# OMODRI_EnDATEnc.net
KiCad netlist of a schematic drawn in Altium Designer
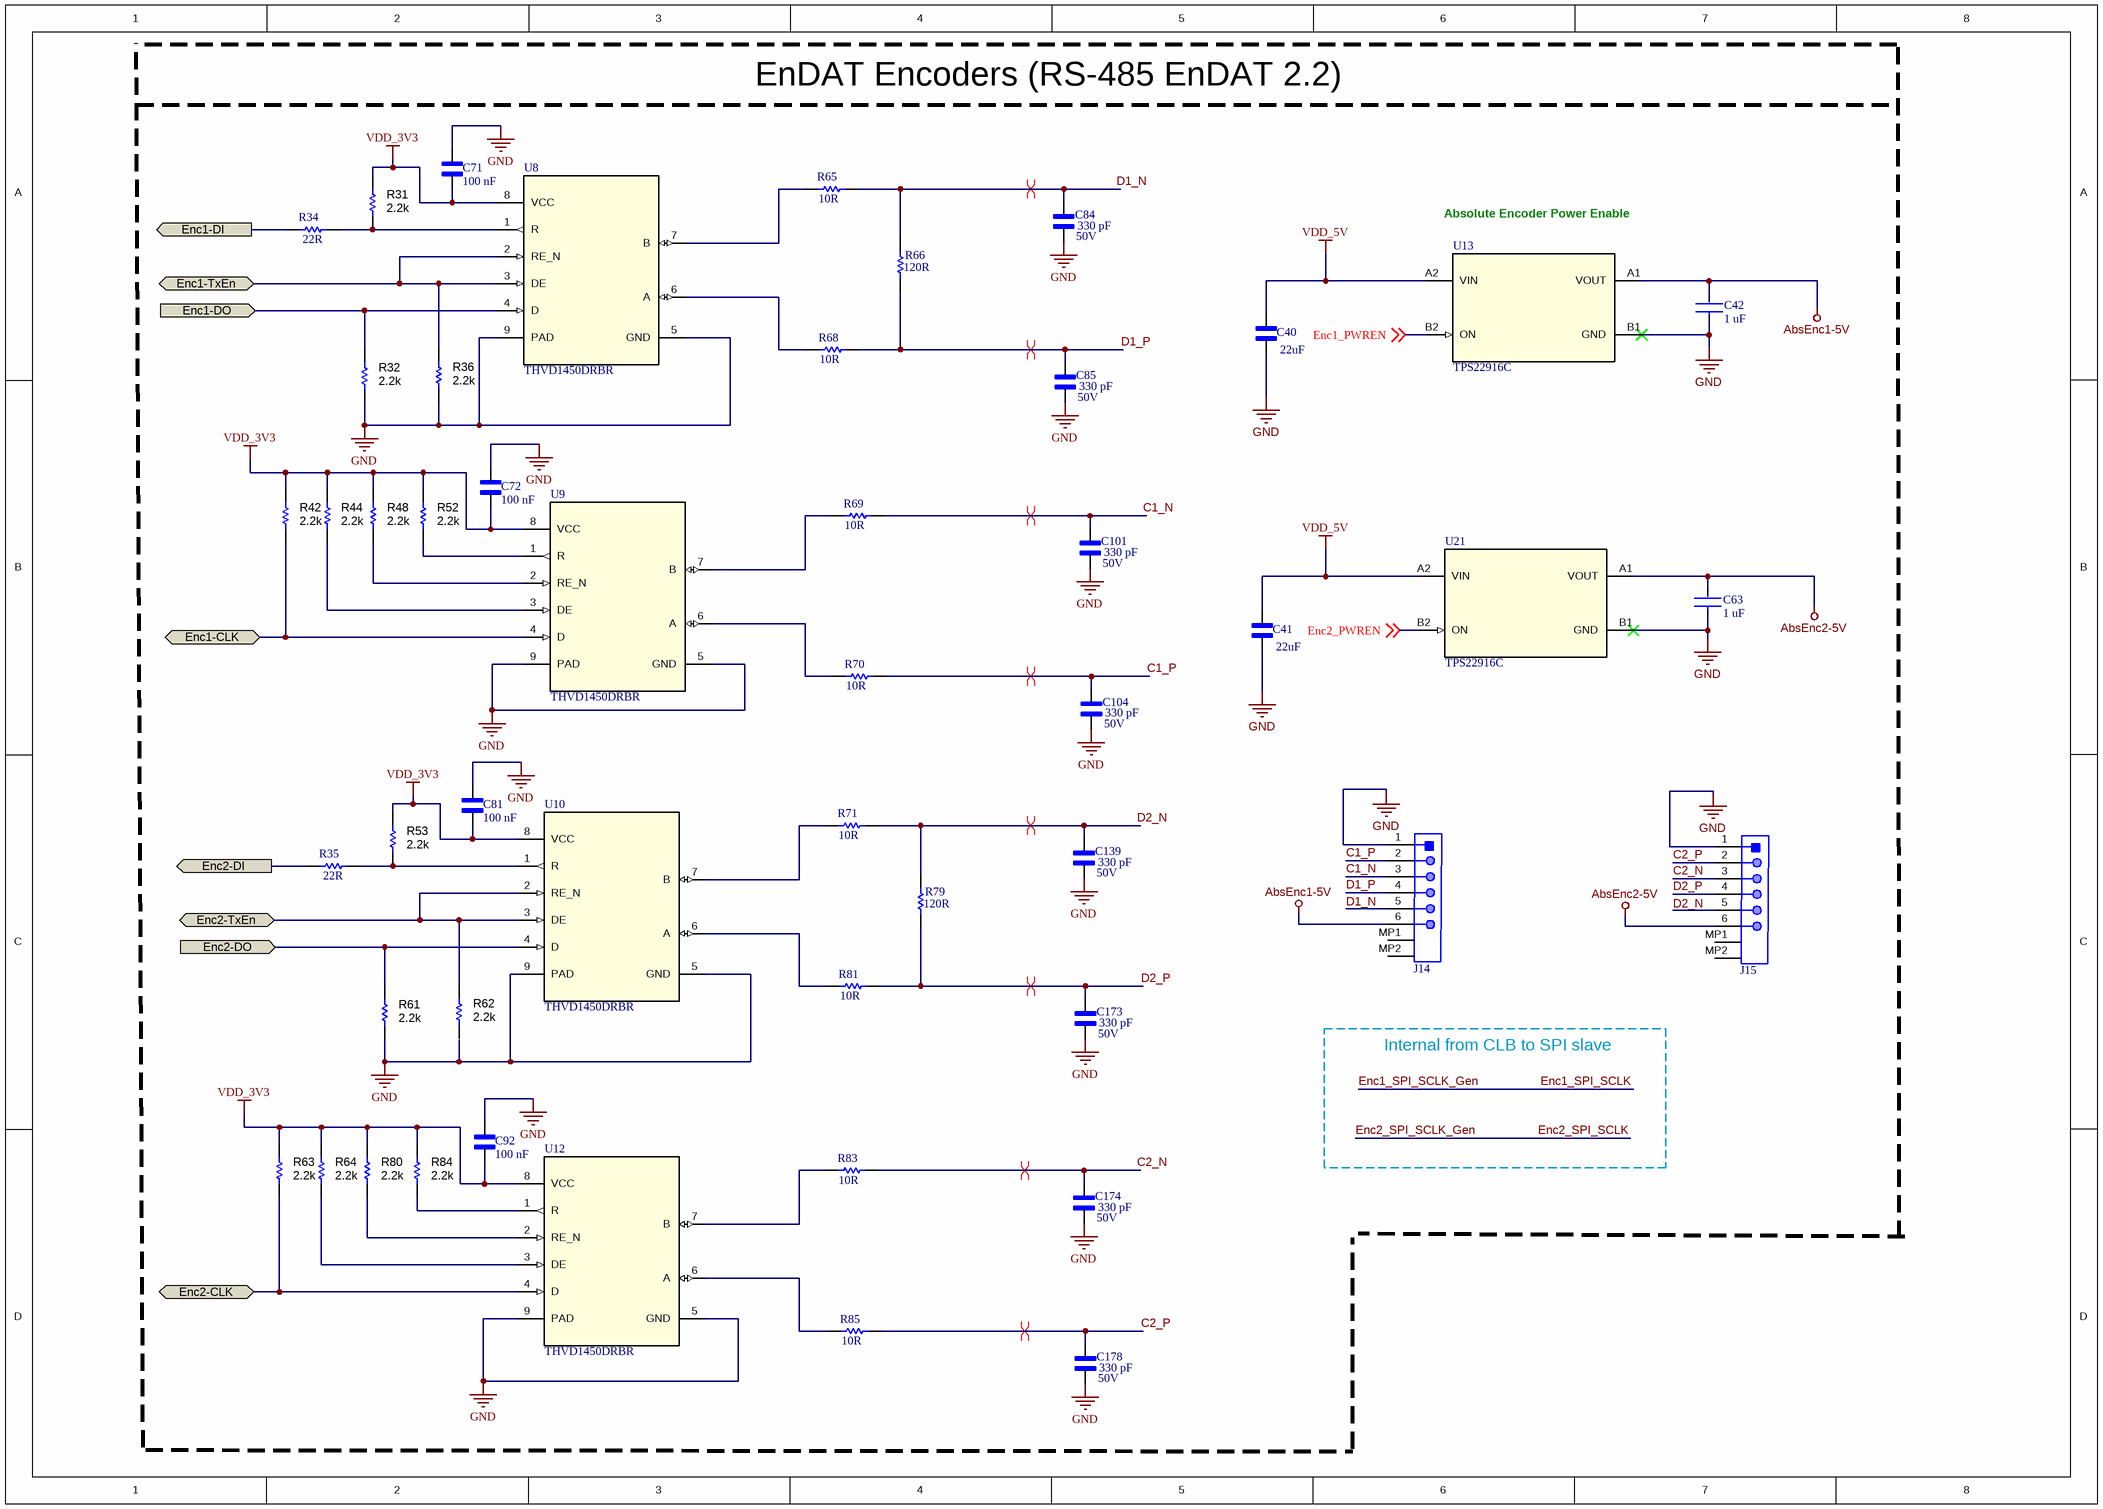
[diagram p0: OMODRI_EnDATEnc.SchDoc]

(export (version "E")
  (design (tool "Eeschema 10.0.6"))
  (components
    (comp (ref "C40")
      (value "22uF")
      (footprint "CAPC1005X55N")
      (description "22µF ±20% 6.3V Ceramic Capacitor X5R 0402 (1005 Metric)")
      (fields (field (name "MP") "CL05A226MQ5N6J8") (field (name "MF") "Samsung Electro-Mechanics"))
      (libsource (lib "CL05A226MQ5N6J8") (part "CL05A226MQ5N6J8"))
    )
    (comp (ref "C41")
      (value "22uF")
      (footprint "CAPC1005X55N")
      (description "22µF ±20% 6.3V Ceramic Capacitor X5R 0402 (1005 Metric)")
      (fields (field (name "MP") "CL05A226MQ5N6J8") (field (name "MF") "Samsung Electro-Mechanics"))
      (libsource (lib "CL05A226MQ5N6J8") (part "CL05A226MQ5N6J8"))
    )
    (comp (ref "C42")
      (value "1 uF")
      (footprint "FP-CC0201-BA-MFG")
      (description "CAP CER 1UF 6.3V X5R 0201")
      (fields (field (name "TOLERANCE") "0.2") (field (name "MANUFACTURER") "Yageo"))
      (libsource (lib "Altium Content Vault") (part "11868f565c42a9108669ba33697ecf6"))
    )
    (comp (ref "C63")
      (value "1 uF")
      (footprint "FP-CC0201-BA-MFG")
      (description "CAP CER 1UF 6.3V X5R 0201")
      (fields (field (name "TOLERANCE") "0.2") (field (name "MANUFACTURER") "Yageo"))
      (libsource (lib "Altium Content Vault") (part "11868f565c42a9108669ba33697ecf6"))
    )
    (comp (ref "C71")
      (value "100 nF")
      (footprint "CAPC0603X33N")
      (description "SMD Capacitor X5R_EIA_ with Capacitance: 0.10uF Tol. 10%. Rated Voltage: 25Vdc")
      (fields (field (name "MF") "Murata") (field (name "MP") "GRM033R61E104KE14D"))
      (libsource (lib "GRM033R61E104KE14D") (part "GRM033R61E104KE14D"))
    )
    (comp (ref "C72")
      (value "100 nF")
      (footprint "CAPC0603X33N")
      (description "SMD Capacitor X5R_EIA_ with Capacitance: 0.10uF Tol. 10%. Rated Voltage: 25Vdc")
      (fields (field (name "MF") "Murata") (field (name "MP") "GRM033R61E104KE14D"))
      (libsource (lib "GRM033R61E104KE14D") (part "GRM033R61E104KE14D"))
    )
    (comp (ref "C81")
      (value "100 nF")
      (footprint "CAPC0603X33N")
      (description "SMD Capacitor X5R_EIA_ with Capacitance: 0.10uF Tol. 10%. Rated Voltage: 25Vdc")
      (fields (field (name "MF") "Murata") (field (name "MP") "GRM033R61E104KE14D"))
      (libsource (lib "GRM033R61E104KE14D") (part "GRM033R61E104KE14D"))
    )
    (comp (ref "C84")
      (value "330 pF")
      (footprint "CAPC0603X33N")
      (description "SMD Capacitor X7R_EIA_ with Capacitance: 330pF Tol. 10%. Rated Voltage: 50Vdc")
      (fields
        (field (name "MP") "GRM033R71H331KA12D")
        (field (name "DIGI-KEY_PART_NUMBER") "490-17085-1-ND")
        (field (name "VOLTAGE") "50V")
      )
      (libsource (lib "GRM033R71H331KA12D") (part "GRM033R71H331KA12D"))
    )
    (comp (ref "C85")
      (value "330 pF")
      (footprint "CAPC0603X33N")
      (description "SMD Capacitor X7R_EIA_ with Capacitance: 330pF Tol. 10%. Rated Voltage: 50Vdc")
      (fields
        (field (name "MP") "GRM033R71H331KA12D")
        (field (name "DIGI-KEY_PART_NUMBER") "490-17085-1-ND")
        (field (name "VOLTAGE") "50V")
      )
      (libsource (lib "GRM033R71H331KA12D") (part "GRM033R71H331KA12D"))
    )
    (comp (ref "C92")
      (value "100 nF")
      (footprint "CAPC0603X33N")
      (description "SMD Capacitor X5R_EIA_ with Capacitance: 0.10uF Tol. 10%. Rated Voltage: 25Vdc")
      (fields (field (name "MF") "Murata") (field (name "MP") "GRM033R61E104KE14D"))
      (libsource (lib "GRM033R61E104KE14D") (part "GRM033R61E104KE14D"))
    )
    (comp (ref "C101")
      (value "330 pF")
      (footprint "CAPC0603X33N")
      (description "SMD Capacitor X7R_EIA_ with Capacitance: 330pF Tol. 10%. Rated Voltage: 50Vdc")
      (fields
        (field (name "MP") "GRM033R71H331KA12D")
        (field (name "DIGI-KEY_PART_NUMBER") "490-17085-1-ND")
        (field (name "VOLTAGE") "50V")
      )
      (libsource (lib "GRM033R71H331KA12D") (part "GRM033R71H331KA12D"))
    )
    (comp (ref "C104")
      (value "330 pF")
      (footprint "CAPC0603X33N")
      (description "SMD Capacitor X7R_EIA_ with Capacitance: 330pF Tol. 10%. Rated Voltage: 50Vdc")
      (fields
        (field (name "MP") "GRM033R71H331KA12D")
        (field (name "DIGI-KEY_PART_NUMBER") "490-17085-1-ND")
        (field (name "VOLTAGE") "50V")
      )
      (libsource (lib "GRM033R71H331KA12D") (part "GRM033R71H331KA12D"))
    )
    (comp (ref "C139")
      (value "330 pF")
      (footprint "CAPC0603X33N")
      (description "SMD Capacitor X7R_EIA_ with Capacitance: 330pF Tol. 10%. Rated Voltage: 50Vdc")
      (fields
        (field (name "MP") "GRM033R71H331KA12D")
        (field (name "DIGI-KEY_PART_NUMBER") "490-17085-1-ND")
        (field (name "VOLTAGE") "50V")
      )
      (libsource (lib "GRM033R71H331KA12D") (part "GRM033R71H331KA12D"))
    )
    (comp (ref "C173")
      (value "330 pF")
      (footprint "CAPC0603X33N")
      (description "SMD Capacitor X7R_EIA_ with Capacitance: 330pF Tol. 10%. Rated Voltage: 50Vdc")
      (fields
        (field (name "MP") "GRM033R71H331KA12D")
        (field (name "DIGI-KEY_PART_NUMBER") "490-17085-1-ND")
        (field (name "VOLTAGE") "50V")
      )
      (libsource (lib "GRM033R71H331KA12D") (part "GRM033R71H331KA12D"))
    )
    (comp (ref "C174")
      (value "330 pF")
      (footprint "CAPC0603X33N")
      (description "SMD Capacitor X7R_EIA_ with Capacitance: 330pF Tol. 10%. Rated Voltage: 50Vdc")
      (fields
        (field (name "MP") "GRM033R71H331KA12D")
        (field (name "DIGI-KEY_PART_NUMBER") "490-17085-1-ND")
        (field (name "VOLTAGE") "50V")
      )
      (libsource (lib "GRM033R71H331KA12D") (part "GRM033R71H331KA12D"))
    )
    (comp (ref "C178")
      (value "330 pF")
      (footprint "CAPC0603X33N")
      (description "SMD Capacitor X7R_EIA_ with Capacitance: 330pF Tol. 10%. Rated Voltage: 50Vdc")
      (fields
        (field (name "MP") "GRM033R71H331KA12D")
        (field (name "DIGI-KEY_PART_NUMBER") "490-17085-1-ND")
        (field (name "VOLTAGE") "50V")
      )
      (libsource (lib "GRM033R71H331KA12D") (part "GRM033R71H331KA12D"))
    )
    (comp (ref "J14")
      (value "Conn_JST_BM06B-GHS-TBT_LF_SN_N_eec")
      (footprint "JST_BM06B-GHS-TBT_LF_SN_N_0")
      (description "CONN HEADER GH TOP 6POS 1.25MM")
      (fields (field (name "MANUFACTURER") "JST") (field (name "DIGIKEY PART NUMBER") "455-1582-1-ND"))
      (libsource (lib "JST_GH") (part "Conn_JST_BM06B-GHS-TBT_LF_SN_N_eec"))
    )
    (comp (ref "J15")
      (value "Conn_JST_BM06B-GHS-TBT_LF_SN_N_eec")
      (footprint "JST_BM06B-GHS-TBT_LF_SN_N_0")
      (description "CONN HEADER GH TOP 6POS 1.25MM")
      (fields (field (name "MANUFACTURER") "JST") (field (name "DIGIKEY PART NUMBER") "455-1582-1-ND"))
      (libsource (lib "JST_GH") (part "Conn_JST_BM06B-GHS-TBT_LF_SN_N_eec"))
    )
    (comp (ref "R31")
      (value "CRCW04022K20JNED")
      (footprint "0402")
      (description "RES, 2.2 k, 5%, 0.063 W, AEC-Q200 Grade 0, 0402")
      (fields (field (name "MANUFACTURER") "Vishay-Dale") (field (name "VALUEDISPLAYED") "2.2k"))
      (libsource (lib "Altium Vault - TI") (part "Resistor"))
    )
    (comp (ref "R32")
      (value "CRCW04022K20JNED")
      (footprint "0402")
      (description "RES, 2.2 k, 5%, 0.063 W, AEC-Q200 Grade 0, 0402")
      (fields (field (name "MANUFACTURER") "Vishay-Dale") (field (name "VALUEDISPLAYED") "2.2k"))
      (libsource (lib "Altium Vault - TI") (part "Resistor"))
    )
    (comp (ref "R34")
      (value "22R")
      (footprint "RESC1005X40X25ML05T05")
      (fields (field (name "MANUFACTURER") "Panasonic") (field (name "PART NUMBER") "ERJ-2GEJ220X"))
      (libsource (lib "Altium Content Vault") (part "RES"))
    )
    (comp (ref "R35")
      (value "22R")
      (footprint "RESC1005X40X25ML05T05")
      (fields (field (name "MANUFACTURER") "Panasonic") (field (name "PART NUMBER") "ERJ-2GEJ220X"))
      (libsource (lib "Altium Content Vault") (part "RES"))
    )
    (comp (ref "R36")
      (value "CRCW04022K20JNED")
      (footprint "0402")
      (description "RES, 2.2 k, 5%, 0.063 W, AEC-Q200 Grade 0, 0402")
      (fields (field (name "MANUFACTURER") "Vishay-Dale") (field (name "VALUEDISPLAYED") "2.2k"))
      (libsource (lib "Altium Vault - TI") (part "Resistor"))
    )
    (comp (ref "R42")
      (value "CRCW04022K20JNED")
      (footprint "0402")
      (description "RES, 2.2 k, 5%, 0.063 W, AEC-Q200 Grade 0, 0402")
      (fields (field (name "MANUFACTURER") "Vishay-Dale") (field (name "VALUEDISPLAYED") "2.2k"))
      (libsource (lib "Altium Vault - TI") (part "Resistor"))
    )
    (comp (ref "R44")
      (value "CRCW04022K20JNED")
      (footprint "0402")
      (description "RES, 2.2 k, 5%, 0.063 W, AEC-Q200 Grade 0, 0402")
      (fields (field (name "MANUFACTURER") "Vishay-Dale") (field (name "VALUEDISPLAYED") "2.2k"))
      (libsource (lib "Altium Vault - TI") (part "Resistor"))
    )
    (comp (ref "R48")
      (value "CRCW04022K20JNED")
      (footprint "0402")
      (description "RES, 2.2 k, 5%, 0.063 W, AEC-Q200 Grade 0, 0402")
      (fields (field (name "MANUFACTURER") "Vishay-Dale") (field (name "VALUEDISPLAYED") "2.2k"))
      (libsource (lib "Altium Vault - TI") (part "Resistor"))
    )
    (comp (ref "R52")
      (value "CRCW04022K20JNED")
      (footprint "0402")
      (description "RES, 2.2 k, 5%, 0.063 W, AEC-Q200 Grade 0, 0402")
      (fields (field (name "MANUFACTURER") "Vishay-Dale") (field (name "VALUEDISPLAYED") "2.2k"))
      (libsource (lib "Altium Vault - TI") (part "Resistor"))
    )
    (comp (ref "R53")
      (value "CRCW04022K20JNED")
      (footprint "0402")
      (description "RES, 2.2 k, 5%, 0.063 W, AEC-Q200 Grade 0, 0402")
      (fields (field (name "MANUFACTURER") "Vishay-Dale") (field (name "VALUEDISPLAYED") "2.2k"))
      (libsource (lib "Altium Vault - TI") (part "Resistor"))
    )
    (comp (ref "R61")
      (value "CRCW04022K20JNED")
      (footprint "0402")
      (description "RES, 2.2 k, 5%, 0.063 W, AEC-Q200 Grade 0, 0402")
      (fields (field (name "MANUFACTURER") "Vishay-Dale") (field (name "VALUEDISPLAYED") "2.2k"))
      (libsource (lib "Altium Vault - TI") (part "Resistor"))
    )
    (comp (ref "R62")
      (value "CRCW04022K20JNED")
      (footprint "0402")
      (description "RES, 2.2 k, 5%, 0.063 W, AEC-Q200 Grade 0, 0402")
      (fields (field (name "MANUFACTURER") "Vishay-Dale") (field (name "VALUEDISPLAYED") "2.2k"))
      (libsource (lib "Altium Vault - TI") (part "Resistor"))
    )
    (comp (ref "R63")
      (value "CRCW04022K20JNED")
      (footprint "0402")
      (description "RES, 2.2 k, 5%, 0.063 W, AEC-Q200 Grade 0, 0402")
      (fields (field (name "MANUFACTURER") "Vishay-Dale") (field (name "VALUEDISPLAYED") "2.2k"))
      (libsource (lib "Altium Vault - TI") (part "Resistor"))
    )
    (comp (ref "R64")
      (value "CRCW04022K20JNED")
      (footprint "0402")
      (description "RES, 2.2 k, 5%, 0.063 W, AEC-Q200 Grade 0, 0402")
      (fields (field (name "MANUFACTURER") "Vishay-Dale") (field (name "VALUEDISPLAYED") "2.2k"))
      (libsource (lib "Altium Vault - TI") (part "Resistor"))
    )
    (comp (ref "R65")
      (value "CRCW040210R0FKEDHP")
      (footprint "RESC1005X40X25ML05T10")
      (description "SMD Chip Resistor, 0402 [1005 Metric], 10 ohm, CRCW-HP e3 Series, 50 V, Thick Film, 200 mW")
      (fields
        (field (name "MANUFACTURER") "Vishay Dale")
        (field (name "TOLERANCE") "1%")
        (field (name "RESISTANCE") "10R")
      )
      (libsource (lib "Vishay-Resistor") (part "CRCW040210R0FKEDHP"))
    )
    (comp (ref "R66")
      (value "CRCW0402120RJNEDHP")
      (footprint "RESC1005X40X25ML05T10")
      (description "RES SMD 120 OHM 5% 1/5W 0402")
      (fields
        (field (name "MANUFACTURER") "Vishay Dale")
        (field (name "TOLERANCE") "5%")
        (field (name "RESISTANCE") "120R")
      )
      (libsource (lib "Vishay-Resistor") (part "CRCW0402120RJNEDHP"))
    )
    (comp (ref "R68")
      (value "CRCW040210R0FKEDHP")
      (footprint "RESC1005X40X25ML05T10")
      (description "SMD Chip Resistor, 0402 [1005 Metric], 10 ohm, CRCW-HP e3 Series, 50 V, Thick Film, 200 mW")
      (fields
        (field (name "MANUFACTURER") "Vishay Dale")
        (field (name "TOLERANCE") "1%")
        (field (name "RESISTANCE") "10R")
      )
      (libsource (lib "Vishay-Resistor") (part "CRCW040210R0FKEDHP"))
    )
    (comp (ref "R69")
      (value "CRCW040210R0FKEDHP")
      (footprint "RESC1005X40X25ML05T10")
      (description "SMD Chip Resistor, 0402 [1005 Metric], 10 ohm, CRCW-HP e3 Series, 50 V, Thick Film, 200 mW")
      (fields
        (field (name "MANUFACTURER") "Vishay Dale")
        (field (name "TOLERANCE") "1%")
        (field (name "RESISTANCE") "10R")
      )
      (libsource (lib "Vishay-Resistor") (part "CRCW040210R0FKEDHP"))
    )
    (comp (ref "R70")
      (value "CRCW040210R0FKEDHP")
      (footprint "RESC1005X40X25ML05T10")
      (description "SMD Chip Resistor, 0402 [1005 Metric], 10 ohm, CRCW-HP e3 Series, 50 V, Thick Film, 200 mW")
      (fields
        (field (name "MANUFACTURER") "Vishay Dale")
        (field (name "TOLERANCE") "1%")
        (field (name "RESISTANCE") "10R")
      )
      (libsource (lib "Vishay-Resistor") (part "CRCW040210R0FKEDHP"))
    )
    (comp (ref "R71")
      (value "CRCW040210R0FKEDHP")
      (footprint "RESC1005X40X25ML05T10")
      (description "SMD Chip Resistor, 0402 [1005 Metric], 10 ohm, CRCW-HP e3 Series, 50 V, Thick Film, 200 mW")
      (fields
        (field (name "MANUFACTURER") "Vishay Dale")
        (field (name "TOLERANCE") "1%")
        (field (name "RESISTANCE") "10R")
      )
      (libsource (lib "Vishay-Resistor") (part "CRCW040210R0FKEDHP"))
    )
    (comp (ref "R79")
      (value "CRCW0402120RJNEDHP")
      (footprint "RESC1005X40X25ML05T10")
      (description "RES SMD 120 OHM 5% 1/5W 0402")
      (fields
        (field (name "MANUFACTURER") "Vishay Dale")
        (field (name "TOLERANCE") "5%")
        (field (name "RESISTANCE") "120R")
      )
      (libsource (lib "Vishay-Resistor") (part "CRCW0402120RJNEDHP"))
    )
    (comp (ref "R80")
      (value "CRCW04022K20JNED")
      (footprint "0402")
      (description "RES, 2.2 k, 5%, 0.063 W, AEC-Q200 Grade 0, 0402")
      (fields (field (name "MANUFACTURER") "Vishay-Dale") (field (name "VALUEDISPLAYED") "2.2k"))
      (libsource (lib "Altium Vault - TI") (part "Resistor"))
    )
    (comp (ref "R81")
      (value "CRCW040210R0FKEDHP")
      (footprint "RESC1005X40X25ML05T10")
      (description "SMD Chip Resistor, 0402 [1005 Metric], 10 ohm, CRCW-HP e3 Series, 50 V, Thick Film, 200 mW")
      (fields
        (field (name "MANUFACTURER") "Vishay Dale")
        (field (name "TOLERANCE") "1%")
        (field (name "RESISTANCE") "10R")
      )
      (libsource (lib "Vishay-Resistor") (part "CRCW040210R0FKEDHP"))
    )
    (comp (ref "R83")
      (value "CRCW040210R0FKEDHP")
      (footprint "RESC1005X40X25ML05T10")
      (description "SMD Chip Resistor, 0402 [1005 Metric], 10 ohm, CRCW-HP e3 Series, 50 V, Thick Film, 200 mW")
      (fields
        (field (name "MANUFACTURER") "Vishay Dale")
        (field (name "TOLERANCE") "1%")
        (field (name "RESISTANCE") "10R")
      )
      (libsource (lib "Vishay-Resistor") (part "CRCW040210R0FKEDHP"))
    )
    (comp (ref "R84")
      (value "CRCW04022K20JNED")
      (footprint "0402")
      (description "RES, 2.2 k, 5%, 0.063 W, AEC-Q200 Grade 0, 0402")
      (fields (field (name "MANUFACTURER") "Vishay-Dale") (field (name "VALUEDISPLAYED") "2.2k"))
      (libsource (lib "Altium Vault - TI") (part "Resistor"))
    )
    (comp (ref "R85")
      (value "CRCW040210R0FKEDHP")
      (footprint "RESC1005X40X25ML05T10")
      (description "SMD Chip Resistor, 0402 [1005 Metric], 10 ohm, CRCW-HP e3 Series, 50 V, Thick Film, 200 mW")
      (fields
        (field (name "MANUFACTURER") "Vishay Dale")
        (field (name "TOLERANCE") "1%")
        (field (name "RESISTANCE") "10R")
      )
      (libsource (lib "Vishay-Resistor") (part "CRCW040210R0FKEDHP"))
    )
    (comp (ref "U8")
      (value "THVD1450DRBR")
      (footprint "DRB0008F")
      (fields (field (name "MANUFACTURER") "Texas Instruments"))
      (libsource (lib "Texas_Instruments") (part "THVD1450DRBR"))
    )
    (comp (ref "U9")
      (value "THVD1450DRBR")
      (footprint "DRB0008F")
      (fields (field (name "MANUFACTURER") "Texas Instruments"))
      (libsource (lib "Texas_Instruments") (part "THVD1450DRBR"))
    )
    (comp (ref "U10")
      (value "THVD1450DRBR")
      (footprint "DRB0008F")
      (fields (field (name "MANUFACTURER") "Texas Instruments"))
      (libsource (lib "Texas_Instruments") (part "THVD1450DRBR"))
    )
    (comp (ref "U12")
      (value "THVD1450DRBR")
      (footprint "DRB0008F")
      (fields (field (name "MANUFACTURER") "Texas Instruments"))
      (libsource (lib "Texas_Instruments") (part "THVD1450DRBR"))
    )
    (comp (ref "U13")
      (value "TPS22916C")
      (footprint "YFP0004ABAB")
      (description "TPS22916CY Single-Channel Ultra-Low Leakage Load Switch 2A 60 mO 1V to 5.5V 4-Pin DSBGA T/R")
      (fields
        (field (name "MANUFACTURER") "Texas Instruments")
        (field (name "MANUFACTURER PART NUMBER") "TPS22916CYFPR")
      )
      (libsource (lib "Texas_Instruments") (part "TPS22916C"))
    )
    (comp (ref "U21")
      (value "TPS22916C")
      (footprint "YFP0004ABAB")
      (description "TPS22916CY Single-Channel Ultra-Low Leakage Load Switch 2A 60 mO 1V to 5.5V 4-Pin DSBGA T/R")
      (fields
        (field (name "MANUFACTURER") "Texas Instruments")
        (field (name "MANUFACTURER PART NUMBER") "TPS22916CYFPR")
      )
      (libsource (lib "Texas_Instruments") (part "TPS22916C"))
    )
  )
  (nets
    (net (code "1") (name "/C1_N") (class "Default")
      (node (ref "C101") (pin "2") (pinfunction "2_2") (pintype "passive"))
      (node (ref "J14") (pin "3") (pinfunction "3_3") (pintype "passive"))
      (node (ref "R69") (pin "2") (pinfunction "2_2") (pintype "passive"))
    )
    (net (code "2") (name "/C1_P") (class "Default")
      (node (ref "C104") (pin "2") (pinfunction "2_2") (pintype "passive"))
      (node (ref "J14") (pin "2") (pinfunction "2_2") (pintype "passive"))
      (node (ref "R70") (pin "2") (pinfunction "2_2") (pintype "passive"))
    )
    (net (code "3") (name "/C2_N") (class "Default")
      (node (ref "C174") (pin "2") (pinfunction "2_2") (pintype "passive"))
      (node (ref "J15") (pin "3") (pinfunction "3_3") (pintype "passive"))
      (node (ref "R83") (pin "2") (pinfunction "2_2") (pintype "passive"))
    )
    (net (code "4") (name "/C2_P") (class "Default")
      (node (ref "C178") (pin "2") (pinfunction "2_2") (pintype "passive"))
      (node (ref "J15") (pin "2") (pinfunction "2_2") (pintype "passive"))
      (node (ref "R85") (pin "2") (pinfunction "2_2") (pintype "passive"))
    )
    (net (code "5") (name "/D1_N") (class "Default")
      (node (ref "C84") (pin "2") (pinfunction "2_2") (pintype "passive"))
      (node (ref "R65") (pin "2") (pinfunction "2_2") (pintype "passive"))
      (node (ref "R66") (pin "2") (pinfunction "2_2") (pintype "passive"))
    )
    (net (code "6") (name "/D1_P") (class "Default")
      (node (ref "C85") (pin "2") (pinfunction "2_2") (pintype "passive"))
      (node (ref "J14") (pin "4") (pinfunction "4_4") (pintype "passive"))
      (node (ref "R66") (pin "1") (pinfunction "1_1") (pintype "passive"))
      (node (ref "R68") (pin "2") (pinfunction "2_2") (pintype "passive"))
    )
    (net (code "7") (name "/D2_N") (class "Default")
      (node (ref "C139") (pin "2") (pinfunction "2_2") (pintype "passive"))
      (node (ref "R71") (pin "2") (pinfunction "2_2") (pintype "passive"))
      (node (ref "R79") (pin "2") (pinfunction "2_2") (pintype "passive"))
    )
    (net (code "8") (name "/D2_P") (class "Default")
      (node (ref "C173") (pin "2") (pinfunction "2_2") (pintype "passive"))
      (node (ref "J15") (pin "4") (pinfunction "4_4") (pintype "passive"))
      (node (ref "R79") (pin "1") (pinfunction "1_1") (pintype "passive"))
      (node (ref "R81") (pin "2") (pinfunction "2_2") (pintype "passive"))
    )
    (net (code "9") (name "/Enc1-CLK") (class "Default")
      (node (ref "R42") (pin "1") (pinfunction "1_1") (pintype "passive"))
      (node (ref "U9") (pin "4") (pinfunction "D_4") (pintype "input"))
    )
    (net (code "10") (name "/Enc1-DI") (class "Default")
      (node (ref "R34") (pin "1") (pinfunction "1_1") (pintype "passive"))
    )
    (net (code "11") (name "/Enc1-DO") (class "Default")
      (node (ref "R32") (pin "2") (pinfunction "2_2") (pintype "passive"))
      (node (ref "U8") (pin "4") (pinfunction "D_4") (pintype "input"))
    )
    (net (code "12") (name "/Enc1-TxEn") (class "Default")
      (node (ref "R36") (pin "2") (pinfunction "2_2") (pintype "passive"))
      (node (ref "U8") (pin "2") (pinfunction "RE_N_2") (pintype "input"))
      (node (ref "U8") (pin "3") (pinfunction "DE_3") (pintype "input"))
    )
    (net (code "14") (name "/Enc2-CLK") (class "Default")
      (node (ref "R63") (pin "1") (pinfunction "1_1") (pintype "passive"))
      (node (ref "U12") (pin "4") (pinfunction "D_4") (pintype "input"))
    )
    (net (code "15") (name "/Enc2-DI") (class "Default")
      (node (ref "R35") (pin "1") (pinfunction "1_1") (pintype "passive"))
    )
    (net (code "16") (name "/Enc2-DO") (class "Default")
      (node (ref "R61") (pin "2") (pinfunction "2_2") (pintype "passive"))
      (node (ref "U10") (pin "4") (pinfunction "D_4") (pintype "input"))
    )
    (net (code "17") (name "/Enc2-TxEn") (class "Default")
      (node (ref "R62") (pin "2") (pinfunction "2_2") (pintype "passive"))
      (node (ref "U10") (pin "2") (pinfunction "RE_N_2") (pintype "input"))
      (node (ref "U10") (pin "3") (pinfunction "DE_3") (pintype "input"))
    )
    (net (code "19") (name "AbsEnc1-5V") (class "Default")
      (node (ref "C42") (pin "2") (pinfunction "2_2") (pintype "passive"))
      (node (ref "J14") (pin "6") (pinfunction "6_6") (pintype "passive"))
      (node (ref "U13") (pin "A1") (pinfunction "VOUT_A1") (pintype "power_in"))
    )
    (net (code "20") (name "AbsEnc2-5V") (class "Default")
      (node (ref "C63") (pin "2") (pinfunction "2_2") (pintype "passive"))
      (node (ref "J15") (pin "6") (pinfunction "6_6") (pintype "passive"))
      (node (ref "U21") (pin "A1") (pinfunction "VOUT_A1") (pintype "power_in"))
    )
    (net (code "21") (name "Enc1_PWREN") (class "Default")
      (node (ref "U13") (pin "B2") (pinfunction "ON_B2") (pintype "input"))
    )
    (net (code "22") (name "Enc2_PWREN") (class "Default")
      (node (ref "U21") (pin "B2") (pinfunction "ON_B2") (pintype "input"))
    )
    (net (code "23") (name "GND") (class "Default")
      (node (ref "C101") (pin "1") (pinfunction "1_1") (pintype "passive"))
      (node (ref "C104") (pin "1") (pinfunction "1_1") (pintype "passive"))
      (node (ref "C139") (pin "1") (pinfunction "1_1") (pintype "passive"))
      (node (ref "C173") (pin "1") (pinfunction "1_1") (pintype "passive"))
      (node (ref "C174") (pin "1") (pinfunction "1_1") (pintype "passive"))
      (node (ref "C178") (pin "1") (pinfunction "1_1") (pintype "passive"))
      (node (ref "C40") (pin "1") (pinfunction "1_1") (pintype "passive"))
      (node (ref "C41") (pin "1") (pinfunction "1_1") (pintype "passive"))
      (node (ref "C42") (pin "1") (pinfunction "1_1") (pintype "passive"))
      (node (ref "C63") (pin "1") (pinfunction "1_1") (pintype "passive"))
      (node (ref "C71") (pin "2") (pinfunction "2_2") (pintype "passive"))
      (node (ref "C72") (pin "2") (pinfunction "2_2") (pintype "passive"))
      (node (ref "C81") (pin "2") (pinfunction "2_2") (pintype "passive"))
      (node (ref "C84") (pin "1") (pinfunction "1_1") (pintype "passive"))
      (node (ref "C85") (pin "1") (pinfunction "1_1") (pintype "passive"))
      (node (ref "C92") (pin "2") (pinfunction "2_2") (pintype "passive"))
      (node (ref "J14") (pin "1") (pinfunction "1_1") (pintype "passive"))
      (node (ref "J15") (pin "1") (pinfunction "1_1") (pintype "passive"))
      (node (ref "R32") (pin "1") (pinfunction "1_1") (pintype "passive"))
      (node (ref "R61") (pin "1") (pinfunction "1_1") (pintype "passive"))
      (node (ref "U10") (pin "5") (pinfunction "GND_5") (pintype "power_in"))
      (node (ref "U10") (pin "9") (pinfunction "PAD_9") (pintype "passive"))
      (node (ref "U12") (pin "5") (pinfunction "GND_5") (pintype "power_in"))
      (node (ref "U12") (pin "9") (pinfunction "PAD_9") (pintype "passive"))
      (node (ref "U13") (pin "B1") (pinfunction "GND_B1") (pintype "power_in"))
      (node (ref "U21") (pin "B1") (pinfunction "GND_B1") (pintype "power_in"))
      (node (ref "U8") (pin "5") (pinfunction "GND_5") (pintype "power_in"))
      (node (ref "U8") (pin "9") (pinfunction "PAD_9") (pintype "passive"))
      (node (ref "U9") (pin "5") (pinfunction "GND_5") (pintype "power_in"))
      (node (ref "U9") (pin "9") (pinfunction "PAD_9") (pintype "passive"))
    )
    (net (code "24") (name "Net-(U8-A)") (class "Default")
      (node (ref "R68") (pin "1") (pinfunction "1_1") (pintype "passive"))
      (node (ref "U8") (pin "6") (pinfunction "A_6") (pintype "bidirectional"))
    )
    (net (code "25") (name "Net-(U8-B)") (class "Default")
      (node (ref "R65") (pin "1") (pinfunction "1_1") (pintype "passive"))
      (node (ref "U8") (pin "7") (pinfunction "B_7") (pintype "bidirectional"))
    )
    (net (code "26") (name "Net-(U8-R)") (class "Default")
      (node (ref "R31") (pin "1") (pinfunction "1_1") (pintype "passive"))
      (node (ref "R34") (pin "2") (pinfunction "2_2") (pintype "passive"))
      (node (ref "U8") (pin "1") (pinfunction "R_1") (pintype "output"))
    )
    (net (code "27") (name "Net-(U9-A)") (class "Default")
      (node (ref "R70") (pin "1") (pinfunction "1_1") (pintype "passive"))
      (node (ref "U9") (pin "6") (pinfunction "A_6") (pintype "bidirectional"))
    )
    (net (code "28") (name "Net-(U9-B)") (class "Default")
      (node (ref "R69") (pin "1") (pinfunction "1_1") (pintype "passive"))
      (node (ref "U9") (pin "7") (pinfunction "B_7") (pintype "bidirectional"))
    )
    (net (code "29") (name "Net-(U9-DE)") (class "Default")
      (node (ref "R44") (pin "1") (pinfunction "1_1") (pintype "passive"))
      (node (ref "U9") (pin "3") (pinfunction "DE_3") (pintype "input"))
    )
    (net (code "30") (name "Net-(U9-R)") (class "Default")
      (node (ref "R52") (pin "1") (pinfunction "1_1") (pintype "passive"))
      (node (ref "U9") (pin "1") (pinfunction "R_1") (pintype "output"))
    )
    (net (code "31") (name "Net-(U9-RE_N)") (class "Default")
      (node (ref "R48") (pin "1") (pinfunction "1_1") (pintype "passive"))
      (node (ref "U9") (pin "2") (pinfunction "RE_N_2") (pintype "input"))
    )
    (net (code "32") (name "Net-(U10-A)") (class "Default")
      (node (ref "R81") (pin "1") (pinfunction "1_1") (pintype "passive"))
      (node (ref "U10") (pin "6") (pinfunction "A_6") (pintype "bidirectional"))
    )
    (net (code "33") (name "Net-(U10-B)") (class "Default")
      (node (ref "R71") (pin "1") (pinfunction "1_1") (pintype "passive"))
      (node (ref "U10") (pin "7") (pinfunction "B_7") (pintype "bidirectional"))
    )
    (net (code "34") (name "Net-(U10-R)") (class "Default")
      (node (ref "R35") (pin "2") (pinfunction "2_2") (pintype "passive"))
      (node (ref "R53") (pin "1") (pinfunction "1_1") (pintype "passive"))
      (node (ref "U10") (pin "1") (pinfunction "R_1") (pintype "output"))
    )
    (net (code "35") (name "Net-(U12-A)") (class "Default")
      (node (ref "R85") (pin "1") (pinfunction "1_1") (pintype "passive"))
      (node (ref "U12") (pin "6") (pinfunction "A_6") (pintype "bidirectional"))
    )
    (net (code "36") (name "Net-(U12-B)") (class "Default")
      (node (ref "R83") (pin "1") (pinfunction "1_1") (pintype "passive"))
      (node (ref "U12") (pin "7") (pinfunction "B_7") (pintype "bidirectional"))
    )
    (net (code "37") (name "Net-(U12-DE)") (class "Default")
      (node (ref "R64") (pin "1") (pinfunction "1_1") (pintype "passive"))
      (node (ref "U12") (pin "3") (pinfunction "DE_3") (pintype "input"))
    )
    (net (code "38") (name "Net-(U12-R)") (class "Default")
      (node (ref "R84") (pin "1") (pinfunction "1_1") (pintype "passive"))
      (node (ref "U12") (pin "1") (pinfunction "R_1") (pintype "output"))
    )
    (net (code "39") (name "Net-(U12-RE_N)") (class "Default")
      (node (ref "R80") (pin "1") (pinfunction "1_1") (pintype "passive"))
      (node (ref "U12") (pin "2") (pinfunction "RE_N_2") (pintype "input"))
    )
    (net (code "40") (name "VDD_3V3") (class "Default")
      (node (ref "C71") (pin "1") (pinfunction "1_1") (pintype "passive"))
      (node (ref "C72") (pin "1") (pinfunction "1_1") (pintype "passive"))
      (node (ref "C81") (pin "1") (pinfunction "1_1") (pintype "passive"))
      (node (ref "C92") (pin "1") (pinfunction "1_1") (pintype "passive"))
      (node (ref "R31") (pin "2") (pinfunction "2_2") (pintype "passive"))
      (node (ref "R42") (pin "2") (pinfunction "2_2") (pintype "passive"))
      (node (ref "R44") (pin "2") (pinfunction "2_2") (pintype "passive"))
      (node (ref "R48") (pin "2") (pinfunction "2_2") (pintype "passive"))
      (node (ref "R52") (pin "2") (pinfunction "2_2") (pintype "passive"))
      (node (ref "R53") (pin "2") (pinfunction "2_2") (pintype "passive"))
      (node (ref "R63") (pin "2") (pinfunction "2_2") (pintype "passive"))
      (node (ref "R64") (pin "2") (pinfunction "2_2") (pintype "passive"))
      (node (ref "R80") (pin "2") (pinfunction "2_2") (pintype "passive"))
      (node (ref "R84") (pin "2") (pinfunction "2_2") (pintype "passive"))
      (node (ref "U10") (pin "8") (pinfunction "VCC_8") (pintype "power_in"))
      (node (ref "U12") (pin "8") (pinfunction "VCC_8") (pintype "power_in"))
      (node (ref "U8") (pin "8") (pinfunction "VCC_8") (pintype "power_in"))
      (node (ref "U9") (pin "8") (pinfunction "VCC_8") (pintype "power_in"))
    )
    (net (code "41") (name "VDD_5V") (class "Default")
      (node (ref "C40") (pin "2") (pinfunction "2_2") (pintype "passive"))
      (node (ref "C41") (pin "2") (pinfunction "2_2") (pintype "passive"))
      (node (ref "U13") (pin "A2") (pinfunction "VIN_A2") (pintype "power_in"))
      (node (ref "U21") (pin "A2") (pinfunction "VIN_A2") (pintype "power_in"))
    )
    (net (code "42") (name "unconnected-(J14-Pad5)") (class "Default")
      (node (ref "J14") (pin "5") (pinfunction "5_5") (pintype "passive"))
    )
    (net (code "43") (name "unconnected-(J14-PadMP1)") (class "Default")
      (node (ref "J14") (pin "MP1") (pinfunction "MP1_MP1") (pintype "passive"))
    )
    (net (code "44") (name "unconnected-(J14-PadMP2)") (class "Default")
      (node (ref "J14") (pin "MP2") (pinfunction "MP2_MP2") (pintype "passive"))
    )
    (net (code "45") (name "unconnected-(J15-Pad5)") (class "Default")
      (node (ref "J15") (pin "5") (pinfunction "5_5") (pintype "passive"))
    )
    (net (code "46") (name "unconnected-(J15-PadMP1)") (class "Default")
      (node (ref "J15") (pin "MP1") (pinfunction "MP1_MP1") (pintype "passive"))
    )
    (net (code "47") (name "unconnected-(J15-PadMP2)") (class "Default")
      (node (ref "J15") (pin "MP2") (pinfunction "MP2_MP2") (pintype "passive"))
    )
    (net (code "48") (name "unconnected-(R36-Pad1)") (class "Default")
      (node (ref "R36") (pin "1") (pinfunction "1_1") (pintype "passive"))
    )
    (net (code "49") (name "unconnected-(R62-Pad1)") (class "Default")
      (node (ref "R62") (pin "1") (pinfunction "1_1") (pintype "passive"))
    )
  )
)
